# PIC32MX.net
KiCad netlist of a schematic drawn in Altium Designer
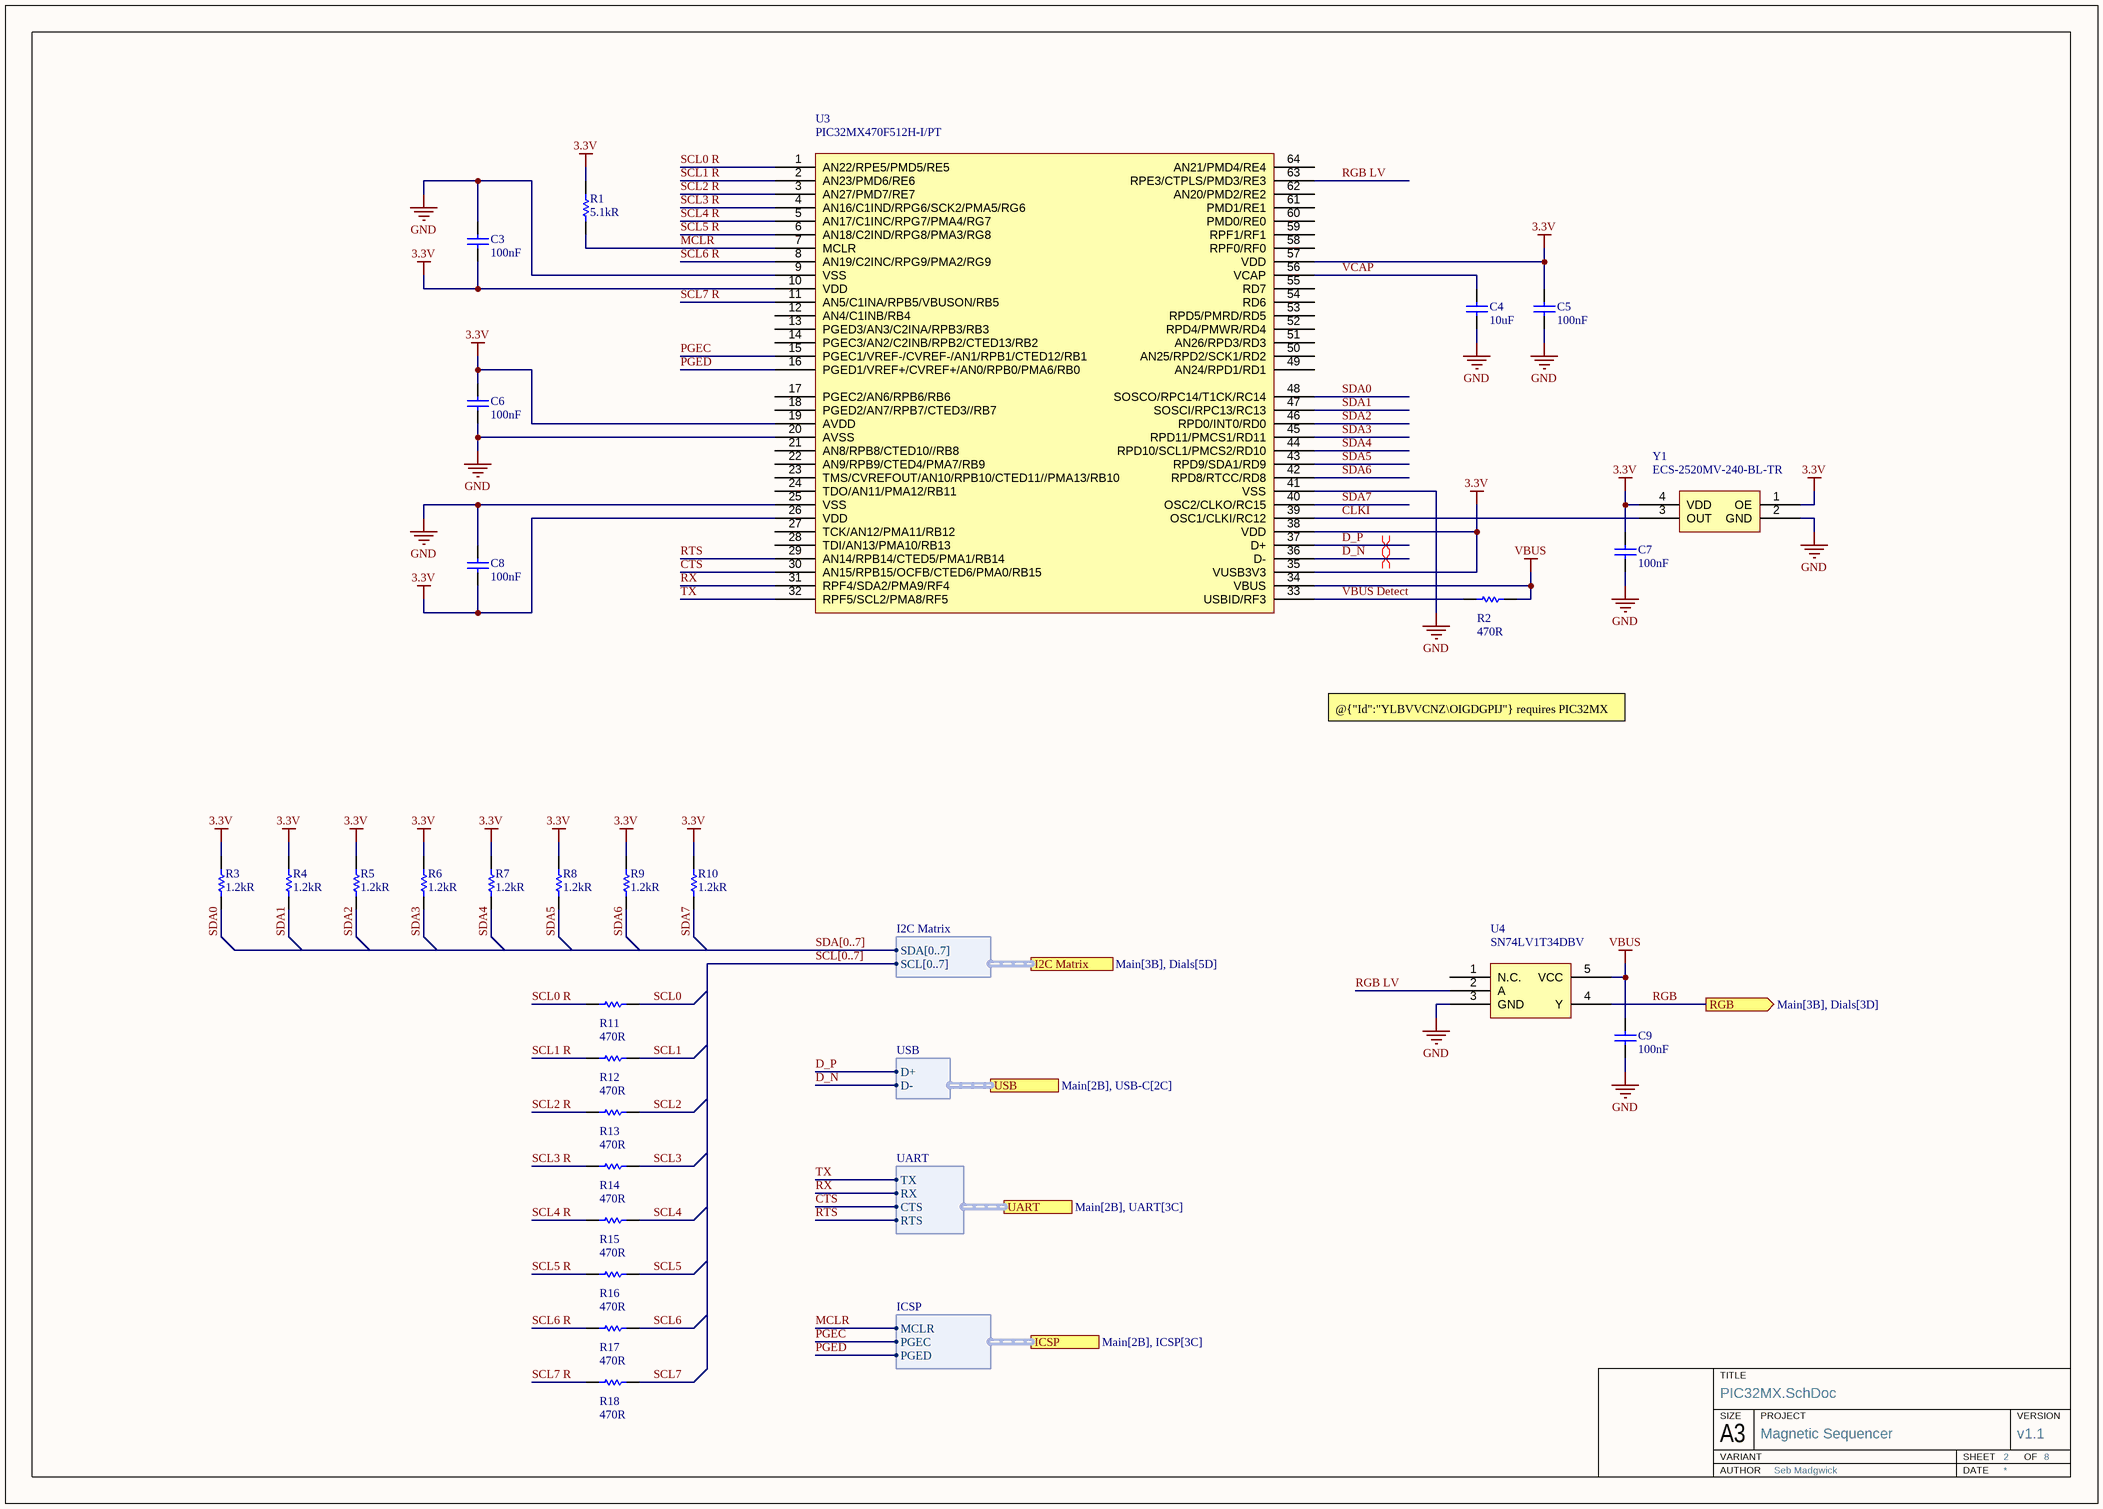
[diagram p0: PIC32MX.SchDoc]

(export (version "E")
  (design (tool "Eeschema 10.0.6"))
  (components
    (comp (ref "C3") (value "100nF") (footprint "Capacitor 0603") (libsource (lib "x-io") (part "Capacitor")))
    (comp (ref "C4") (value "10uF") (footprint "Capacitor 0603") (libsource (lib "x-io") (part "Capacitor")))
    (comp (ref "C5") (value "100nF") (footprint "Capacitor 0603") (libsource (lib "x-io") (part "Capacitor")))
    (comp (ref "C6") (value "100nF") (footprint "Capacitor 0603") (libsource (lib "x-io") (part "Capacitor")))
    (comp (ref "C7") (value "100nF") (footprint "Capacitor 0603") (libsource (lib "x-io") (part "Capacitor")))
    (comp (ref "C8") (value "100nF") (footprint "Capacitor 0603") (libsource (lib "x-io") (part "Capacitor")))
    (comp (ref "C9") (value "100nF") (footprint "Capacitor 0603") (libsource (lib "x-io") (part "Capacitor")))
    (comp (ref "R1") (value "5.1kR") (footprint "Resistor 0603") (libsource (lib "x-io") (part "Resistor")))
    (comp (ref "R2") (value "470R") (footprint "Resistor 0603") (libsource (lib "x-io") (part "Resistor")))
    (comp (ref "R3") (value "1.2kR") (footprint "Resistor 0603") (libsource (lib "x-io") (part "Resistor")))
    (comp (ref "R4") (value "1.2kR") (footprint "Resistor 0603") (libsource (lib "x-io") (part "Resistor")))
    (comp (ref "R5") (value "1.2kR") (footprint "Resistor 0603") (libsource (lib "x-io") (part "Resistor")))
    (comp (ref "R6") (value "1.2kR") (footprint "Resistor 0603") (libsource (lib "x-io") (part "Resistor")))
    (comp (ref "R7") (value "1.2kR") (footprint "Resistor 0603") (libsource (lib "x-io") (part "Resistor")))
    (comp (ref "R8") (value "1.2kR") (footprint "Resistor 0603") (libsource (lib "x-io") (part "Resistor")))
    (comp (ref "R9") (value "1.2kR") (footprint "Resistor 0603") (libsource (lib "x-io") (part "Resistor")))
    (comp (ref "R10") (value "1.2kR") (footprint "Resistor 0603") (libsource (lib "x-io") (part "Resistor")))
    (comp (ref "R11") (value "470R") (footprint "Resistor 0603") (libsource (lib "x-io") (part "Resistor")))
    (comp (ref "R12") (value "470R") (footprint "Resistor 0603") (libsource (lib "x-io") (part "Resistor")))
    (comp (ref "R13") (value "470R") (footprint "Resistor 0603") (libsource (lib "x-io") (part "Resistor")))
    (comp (ref "R14") (value "470R") (footprint "Resistor 0603") (libsource (lib "x-io") (part "Resistor")))
    (comp (ref "R15") (value "470R") (footprint "Resistor 0603") (libsource (lib "x-io") (part "Resistor")))
    (comp (ref "R16") (value "470R") (footprint "Resistor 0603") (libsource (lib "x-io") (part "Resistor")))
    (comp (ref "R17") (value "470R") (footprint "Resistor 0603") (libsource (lib "x-io") (part "Resistor")))
    (comp (ref "R18") (value "470R") (footprint "Resistor 0603") (libsource (lib "x-io") (part "Resistor")))
    (comp (ref "U3")
      (value "PIC32MX470F512H-I/PT")
      (footprint "TQFP-64")
      (libsource (lib "x-io") (part "PIC32MX470F512H"))
    )
    (comp (ref "U4")
      (value "SN74LV1T34DBV")
      (footprint "SOT-23-5")
      (libsource (lib "x-io") (part "SN74LVC1xxx (1 Input)"))
    )
    (comp (ref "Y1")
      (value "ECS-2520MV-240-BL-TR")
      (footprint "ECS-2520MV-240-BL-TR")
      (libsource (lib "x-io") (part "Oscillator"))
    )
  )
  (nets
    (net (code "6") (name "/CLKI") (class "Default")
      (node (ref "U3") (pin "39") (pinfunction "OSC1/CLKI/RC12_39") (pintype "passive"))
      (node (ref "Y1") (pin "3") (pinfunction "OUT_3") (pintype "passive"))
    )
    (net (code "7") (name "/CTS") (class "Default")
      (node (ref "U3") (pin "30") (pinfunction "AN15/RPB15/OCFB/CTED6/PMA0/RB15_30") (pintype "passive"))
    )
    (net (code "8") (name "/D_N") (class "Default")
      (node (ref "U3") (pin "36") (pinfunction "D-_36") (pintype "passive"))
    )
    (net (code "9") (name "/D_P") (class "Default")
      (node (ref "U3") (pin "37") (pinfunction "D+_37") (pintype "passive"))
    )
    (net (code "10") (name "/MCLR") (class "Default")
      (node (ref "R1") (pin "1") (pinfunction "1_1") (pintype "passive"))
      (node (ref "U3") (pin "7") (pinfunction "MCLR_7") (pintype "passive"))
    )
    (net (code "11") (name "/PGEC") (class "Default")
      (node (ref "U3") (pin "15") (pinfunction "PGEC1/VREF-/CVREF-/AN1/RPB1/CTED12/RB1_15") (pintype "passive"))
    )
    (net (code "12") (name "/PGED") (class "Default")
      (node (ref "U3") (pin "16") (pinfunction "PGED1/VREF+/CVREF+/AN0/RPB0/PMA6/RB0_16") (pintype "passive"))
    )
    (net (code "13") (name "/RGB") (class "Default")
      (node (ref "U4") (pin "4") (pinfunction "Y_4") (pintype "passive"))
    )
    (net (code "14") (name "/RGB LV") (class "Default")
      (node (ref "U3") (pin "63") (pinfunction "RPE3/CTPLS/PMD3/RE3_63") (pintype "passive"))
      (node (ref "U4") (pin "2") (pinfunction "A_2") (pintype "passive"))
    )
    (net (code "15") (name "/RTS") (class "Default")
      (node (ref "U3") (pin "29") (pinfunction "AN14/RPB14/CTED5/PMA1/RB14_29") (pintype "passive"))
    )
    (net (code "16") (name "/RX") (class "Default")
      (node (ref "U3") (pin "31") (pinfunction "RPF4/SDA2/PMA9/RF4_31") (pintype "passive"))
    )
    (net (code "17") (name "/SCL0") (class "Default")
      (node (ref "R11") (pin "2") (pinfunction "2_2") (pintype "passive"))
    )
    (net (code "18") (name "/SCL0 R") (class "Default")
      (node (ref "R11") (pin "1") (pinfunction "1_1") (pintype "passive"))
      (node (ref "U3") (pin "1") (pinfunction "AN22/RPE5/PMD5/RE5_1") (pintype "passive"))
    )
    (net (code "19") (name "/SCL1") (class "Default")
      (node (ref "R12") (pin "2") (pinfunction "2_2") (pintype "passive"))
    )
    (net (code "20") (name "/SCL1 R") (class "Default")
      (node (ref "R12") (pin "1") (pinfunction "1_1") (pintype "passive"))
      (node (ref "U3") (pin "2") (pinfunction "AN23/PMD6/RE6_2") (pintype "passive"))
    )
    (net (code "21") (name "/SCL2") (class "Default")
      (node (ref "R13") (pin "2") (pinfunction "2_2") (pintype "passive"))
    )
    (net (code "22") (name "/SCL2 R") (class "Default")
      (node (ref "R13") (pin "1") (pinfunction "1_1") (pintype "passive"))
      (node (ref "U3") (pin "3") (pinfunction "AN27/PMD7/RE7_3") (pintype "passive"))
    )
    (net (code "23") (name "/SCL3") (class "Default")
      (node (ref "R14") (pin "2") (pinfunction "2_2") (pintype "passive"))
    )
    (net (code "24") (name "/SCL3 R") (class "Default")
      (node (ref "R14") (pin "1") (pinfunction "1_1") (pintype "passive"))
      (node (ref "U3") (pin "4") (pinfunction "AN16/C1IND/RPG6/SCK2/PMA5/RG6_4") (pintype "passive"))
    )
    (net (code "25") (name "/SCL4") (class "Default")
      (node (ref "R15") (pin "2") (pinfunction "2_2") (pintype "passive"))
    )
    (net (code "26") (name "/SCL4 R") (class "Default")
      (node (ref "R15") (pin "1") (pinfunction "1_1") (pintype "passive"))
      (node (ref "U3") (pin "5") (pinfunction "AN17/C1INC/RPG7/PMA4/RG7_5") (pintype "passive"))
    )
    (net (code "27") (name "/SCL5") (class "Default")
      (node (ref "R16") (pin "2") (pinfunction "2_2") (pintype "passive"))
    )
    (net (code "28") (name "/SCL5 R") (class "Default")
      (node (ref "R16") (pin "1") (pinfunction "1_1") (pintype "passive"))
      (node (ref "U3") (pin "6") (pinfunction "AN18/C2IND/RPG8/PMA3/RG8_6") (pintype "passive"))
    )
    (net (code "29") (name "/SCL6") (class "Default")
      (node (ref "R17") (pin "2") (pinfunction "2_2") (pintype "passive"))
    )
    (net (code "30") (name "/SCL6 R") (class "Default")
      (node (ref "R17") (pin "1") (pinfunction "1_1") (pintype "passive"))
      (node (ref "U3") (pin "8") (pinfunction "AN19/C2INC/RPG9/PMA2/RG9_8") (pintype "passive"))
    )
    (net (code "31") (name "/SCL7") (class "Default")
      (node (ref "R18") (pin "2") (pinfunction "2_2") (pintype "passive"))
    )
    (net (code "32") (name "/SCL7 R") (class "Default")
      (node (ref "R18") (pin "1") (pinfunction "1_1") (pintype "passive"))
      (node (ref "U3") (pin "11") (pinfunction "AN5/C1INA/RPB5/VBUSON/RB5_11") (pintype "passive"))
    )
    (net (code "34") (name "/SDA0") (class "Default")
      (node (ref "R3") (pin "1") (pinfunction "1_1") (pintype "passive"))
      (node (ref "U3") (pin "48") (pinfunction "SOSCO/RPC14/T1CK/RC14_48") (pintype "passive"))
    )
    (net (code "35") (name "/SDA1") (class "Default")
      (node (ref "R4") (pin "1") (pinfunction "1_1") (pintype "passive"))
      (node (ref "U3") (pin "47") (pinfunction "SOSCI/RPC13/RC13_47") (pintype "passive"))
    )
    (net (code "36") (name "/SDA2") (class "Default")
      (node (ref "R5") (pin "1") (pinfunction "1_1") (pintype "passive"))
      (node (ref "U3") (pin "46") (pinfunction "RPD0/INT0/RD0_46") (pintype "passive"))
    )
    (net (code "37") (name "/SDA3") (class "Default")
      (node (ref "R6") (pin "1") (pinfunction "1_1") (pintype "passive"))
      (node (ref "U3") (pin "45") (pinfunction "RPD11/PMCS1/RD11_45") (pintype "passive"))
    )
    (net (code "38") (name "/SDA4") (class "Default")
      (node (ref "R7") (pin "1") (pinfunction "1_1") (pintype "passive"))
      (node (ref "U3") (pin "44") (pinfunction "RPD10/SCL1/PMCS2/RD10_44") (pintype "passive"))
    )
    (net (code "39") (name "/SDA5") (class "Default")
      (node (ref "R8") (pin "1") (pinfunction "1_1") (pintype "passive"))
      (node (ref "U3") (pin "43") (pinfunction "RPD9/SDA1/RD9_43") (pintype "passive"))
    )
    (net (code "40") (name "/SDA6") (class "Default")
      (node (ref "R9") (pin "1") (pinfunction "1_1") (pintype "passive"))
      (node (ref "U3") (pin "42") (pinfunction "RPD8/RTCC/RD8_42") (pintype "passive"))
    )
    (net (code "41") (name "/SDA7") (class "Default")
      (node (ref "R10") (pin "1") (pinfunction "1_1") (pintype "passive"))
      (node (ref "U3") (pin "40") (pinfunction "OSC2/CLKO/RC15_40") (pintype "passive"))
    )
    (net (code "43") (name "/TX") (class "Default")
      (node (ref "U3") (pin "32") (pinfunction "RPF5/SCL2/PMA8/RF5_32") (pintype "passive"))
    )
    (net (code "44") (name "/VBUS Detect") (class "Default")
      (node (ref "R2") (pin "1") (pinfunction "1_1") (pintype "passive"))
      (node (ref "U3") (pin "33") (pinfunction "USBID/RF3_33") (pintype "passive"))
    )
    (net (code "45") (name "/VCAP") (class "Default")
      (node (ref "C4") (pin "2") (pinfunction "2_2") (pintype "passive"))
      (node (ref "U3") (pin "56") (pinfunction "VCAP_56") (pintype "passive"))
    )
    (net (code "50") (name "3.3V") (class "Default")
      (node (ref "C3") (pin "1") (pinfunction "1_1") (pintype "passive"))
      (node (ref "C5") (pin "2") (pinfunction "2_2") (pintype "passive"))
      (node (ref "C6") (pin "2") (pinfunction "2_2") (pintype "passive"))
      (node (ref "C7") (pin "2") (pinfunction "2_2") (pintype "passive"))
      (node (ref "C8") (pin "1") (pinfunction "1_1") (pintype "passive"))
      (node (ref "R1") (pin "2") (pinfunction "2_2") (pintype "passive"))
      (node (ref "R10") (pin "2") (pinfunction "2_2") (pintype "passive"))
      (node (ref "R3") (pin "2") (pinfunction "2_2") (pintype "passive"))
      (node (ref "R4") (pin "2") (pinfunction "2_2") (pintype "passive"))
      (node (ref "R5") (pin "2") (pinfunction "2_2") (pintype "passive"))
      (node (ref "R6") (pin "2") (pinfunction "2_2") (pintype "passive"))
      (node (ref "R7") (pin "2") (pinfunction "2_2") (pintype "passive"))
      (node (ref "R8") (pin "2") (pinfunction "2_2") (pintype "passive"))
      (node (ref "R9") (pin "2") (pinfunction "2_2") (pintype "passive"))
      (node (ref "U3") (pin "10") (pinfunction "VDD_10") (pintype "passive"))
      (node (ref "U3") (pin "19") (pinfunction "AVDD_19") (pintype "passive"))
      (node (ref "U3") (pin "26") (pinfunction "VDD_26") (pintype "passive"))
      (node (ref "U3") (pin "35") (pinfunction "VUSB3V3_35") (pintype "passive"))
      (node (ref "U3") (pin "38") (pinfunction "VDD_38") (pintype "passive"))
      (node (ref "U3") (pin "57") (pinfunction "VDD_57") (pintype "passive"))
      (node (ref "Y1") (pin "1") (pinfunction "OE_1") (pintype "passive"))
      (node (ref "Y1") (pin "4") (pinfunction "VDD_4") (pintype "passive"))
    )
    (net (code "51") (name "GND") (class "Default")
      (node (ref "C3") (pin "2") (pinfunction "2_2") (pintype "passive"))
      (node (ref "C4") (pin "1") (pinfunction "1_1") (pintype "passive"))
      (node (ref "C5") (pin "1") (pinfunction "1_1") (pintype "passive"))
      (node (ref "C6") (pin "1") (pinfunction "1_1") (pintype "passive"))
      (node (ref "C7") (pin "1") (pinfunction "1_1") (pintype "passive"))
      (node (ref "C8") (pin "2") (pinfunction "2_2") (pintype "passive"))
      (node (ref "C9") (pin "1") (pinfunction "1_1") (pintype "passive"))
      (node (ref "U3") (pin "20") (pinfunction "AVSS_20") (pintype "passive"))
      (node (ref "U3") (pin "25") (pinfunction "VSS_25") (pintype "passive"))
      (node (ref "U3") (pin "41") (pinfunction "VSS_41") (pintype "passive"))
      (node (ref "U3") (pin "9") (pinfunction "VSS_9") (pintype "passive"))
      (node (ref "U4") (pin "3") (pinfunction "GND_3") (pintype "passive"))
      (node (ref "Y1") (pin "2") (pinfunction "GND_2") (pintype "passive"))
    )
    (net (code "52") (name "VBUS") (class "Default")
      (node (ref "C9") (pin "2") (pinfunction "2_2") (pintype "passive"))
      (node (ref "R2") (pin "2") (pinfunction "2_2") (pintype "passive"))
      (node (ref "U3") (pin "34") (pinfunction "VBUS_34") (pintype "passive"))
      (node (ref "U4") (pin "5") (pinfunction "VCC_5") (pintype "passive"))
    )
    (net (code "53") (name "unconnected-(U3-AN4{slash}C1INB{slash}RB4-Pad12)") (class "Default")
      (node (ref "U3") (pin "12") (pinfunction "AN4/C1INB/RB4_12") (pintype "passive"))
    )
    (net (code "54") (name "unconnected-(U3-AN8{slash}RPB8{slash}CTED10{slash}{slash}RB8-Pad21)") (class "Default")
      (node (ref "U3") (pin "21") (pinfunction "AN8/RPB8/CTED10//RB8_21") (pintype "passive"))
    )
    (net (code "55") (name "unconnected-(U3-AN9{slash}RPB9{slash}CTED4{slash}PMA7{slash}RB9-Pad22)") (class "Default")
      (node (ref "U3") (pin "22") (pinfunction "AN9/RPB9/CTED4/PMA7/RB9_22") (pintype "passive"))
    )
    (net (code "56") (name "unconnected-(U3-AN20{slash}PMD2{slash}RE2-Pad62)") (class "Default")
      (node (ref "U3") (pin "62") (pinfunction "AN20/PMD2/RE2_62") (pintype "passive"))
    )
    (net (code "57") (name "unconnected-(U3-AN21{slash}PMD4{slash}RE4-Pad64)") (class "Default")
      (node (ref "U3") (pin "64") (pinfunction "AN21/PMD4/RE4_64") (pintype "passive"))
    )
    (net (code "58") (name "unconnected-(U3-AN24{slash}RPD1{slash}RD1-Pad49)") (class "Default")
      (node (ref "U3") (pin "49") (pinfunction "AN24/RPD1/RD1_49") (pintype "passive"))
    )
    (net (code "59") (name "unconnected-(U3-AN25{slash}RPD2{slash}SCK1{slash}RD2-Pad50)") (class "Default")
      (node (ref "U3") (pin "50") (pinfunction "AN25/RPD2/SCK1/RD2_50") (pintype "passive"))
    )
    (net (code "60") (name "unconnected-(U3-AN26{slash}RPD3{slash}RD3-Pad51)") (class "Default")
      (node (ref "U3") (pin "51") (pinfunction "AN26/RPD3/RD3_51") (pintype "passive"))
    )
    (net (code "61") (name "unconnected-(U3-PGEC2{slash}AN6{slash}RPB6{slash}RB6-Pad17)") (class "Default")
      (node (ref "U3") (pin "17") (pinfunction "PGEC2/AN6/RPB6/RB6_17") (pintype "passive"))
    )
    (net (code "62") (name "unconnected-(U3-PGEC3{slash}AN2{slash}C2INB{slash}RPB2{slash}CTED13{slash}RB2-Pad14)") (class "Default")
      (node (ref "U3") (pin "14") (pinfunction "PGEC3/AN2/C2INB/RPB2/CTED13/RB2_14") (pintype "passive"))
    )
    (net (code "63") (name "unconnected-(U3-PGED2{slash}AN7{slash}RPB7{slash}CTED3{slash}{slash}RB7-Pad18)") (class "Default")
      (node (ref "U3") (pin "18") (pinfunction "PGED2/AN7/RPB7/CTED3//RB7_18") (pintype "passive"))
    )
    (net (code "64") (name "unconnected-(U3-PGED3{slash}AN3{slash}C2INA{slash}RPB3{slash}RB3-Pad13)") (class "Default")
      (node (ref "U3") (pin "13") (pinfunction "PGED3/AN3/C2INA/RPB3/RB3_13") (pintype "passive"))
    )
    (net (code "65") (name "unconnected-(U3-PMD0{slash}RE0-Pad60)") (class "Default")
      (node (ref "U3") (pin "60") (pinfunction "PMD0/RE0_60") (pintype "passive"))
    )
    (net (code "66") (name "unconnected-(U3-PMD1{slash}RE1-Pad61)") (class "Default")
      (node (ref "U3") (pin "61") (pinfunction "PMD1/RE1_61") (pintype "passive"))
    )
    (net (code "67") (name "unconnected-(U3-RD6-Pad54)") (class "Default")
      (node (ref "U3") (pin "54") (pinfunction "RD6_54") (pintype "passive"))
    )
    (net (code "68") (name "unconnected-(U3-RD7-Pad55)") (class "Default")
      (node (ref "U3") (pin "55") (pinfunction "RD7_55") (pintype "passive"))
    )
    (net (code "69") (name "unconnected-(U3-RPD4{slash}PMWR{slash}RD4-Pad52)") (class "Default")
      (node (ref "U3") (pin "52") (pinfunction "RPD4/PMWR/RD4_52") (pintype "passive"))
    )
    (net (code "70") (name "unconnected-(U3-RPD5{slash}PMRD{slash}RD5-Pad53)") (class "Default")
      (node (ref "U3") (pin "53") (pinfunction "RPD5/PMRD/RD5_53") (pintype "passive"))
    )
    (net (code "71") (name "unconnected-(U3-RPF0{slash}RF0-Pad58)") (class "Default")
      (node (ref "U3") (pin "58") (pinfunction "RPF0/RF0_58") (pintype "passive"))
    )
    (net (code "72") (name "unconnected-(U3-RPF1{slash}RF1-Pad59)") (class "Default")
      (node (ref "U3") (pin "59") (pinfunction "RPF1/RF1_59") (pintype "passive"))
    )
    (net (code "73") (name "unconnected-(U3-TCK{slash}AN12{slash}PMA11{slash}RB12-Pad27)") (class "Default")
      (node (ref "U3") (pin "27") (pinfunction "TCK/AN12/PMA11/RB12_27") (pintype "passive"))
    )
    (net (code "74") (name "unconnected-(U3-TDI{slash}AN13{slash}PMA10{slash}RB13-Pad28)") (class "Default")
      (node (ref "U3") (pin "28") (pinfunction "TDI/AN13/PMA10/RB13_28") (pintype "passive"))
    )
    (net (code "75") (name "unconnected-(U3-TDO{slash}AN11{slash}PMA12{slash}RB11-Pad24)") (class "Default")
      (node (ref "U3") (pin "24") (pinfunction "TDO/AN11/PMA12/RB11_24") (pintype "passive"))
    )
    (net (code "76") (name "unconnected-(U3-TMS{slash}CVREFOUT{slash}AN10{slash}RPB10{slash}CTED11{slash}{slash}PMA13{slash}RB10-Pad23)") (class "Default")
      (node (ref "U3") (pin "23") (pinfunction "TMS/CVREFOUT/AN10/RPB10/CTED11//PMA13/RB10_23") (pintype "passive"))
    )
    (net (code "77") (name "unconnected-(U4-N.C.-Pad1)") (class "Default")
      (node (ref "U4") (pin "1") (pinfunction "N.C._1") (pintype "passive"))
    )
  )
)
